# Rumble.net
KiCad netlist of a schematic drawn in Altium Designer
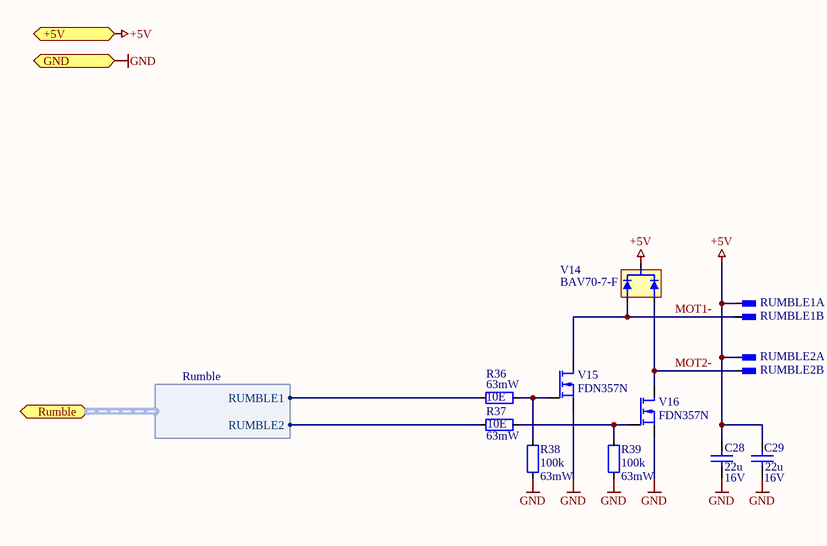
[diagram p0: Rumble.SchDoc]

(export (version "E")
  (design (tool "Eeschema 10.0.6"))
  (components
    (comp (ref "C28")
      (value "22u")
      (footprint "SMD_CAP_0805")
      (description "22µF ±10% 16V Ceramic Capacitor X5R 0805 (2012 Metric)")
      (fields (field (name "VALUE2") "16V") (field (name "Comment") "C_SMD_CER_22U_16V_10%_X5R_0805"))
      (libsource (lib "AM") (part "C_SMD_CER_22U_16V_10%_X5R_0805"))
    )
    (comp (ref "C29")
      (value "22u")
      (footprint "SMD_CAP_0805")
      (description "22µF ±10% 16V Ceramic Capacitor X5R 0805 (2012 Metric)")
      (fields (field (name "VALUE2") "16V") (field (name "Comment") "C_SMD_CER_22U_16V_10%_X5R_0805"))
      (libsource (lib "AM") (part "C_SMD_CER_22U_16V_10%_X5R_0805"))
    )
    (comp (ref "R36")
      (value "10E")
      (footprint "SMD_RES_0402")
      (description "10 Ohms ±0.5% 0.063W, 1/16W Chip Resistor 0402 (1005 Metric) Thin Film")
      (fields
        (field (name "VALUE2") "63mW")
        (field (name "Comment") "R_SMD_THINFILM_10E_0W063_0%5_50PPM_0402")
      )
      (libsource (lib "AM") (part "R_SMD_THINFILM_10E_0W063_0%5_50PPM_0402"))
    )
    (comp (ref "R37")
      (value "10E")
      (footprint "SMD_RES_0402")
      (description "10 Ohms ±0.5% 0.063W, 1/16W Chip Resistor 0402 (1005 Metric) Thin Film")
      (fields
        (field (name "VALUE2") "63mW")
        (field (name "Comment") "R_SMD_THINFILM_10E_0W063_0%5_50PPM_0402")
      )
      (libsource (lib "AM") (part "R_SMD_THINFILM_10E_0W063_0%5_50PPM_0402"))
    )
    (comp (ref "R38")
      (value "100k")
      (footprint "SMD_RES_0402")
      (description "100 kOhms ±1% 0.063W, 1/16W Chip Resistor 0402 (1005 Metric) Thin Film")
      (fields
        (field (name "VALUE2") "63mW")
        (field (name "Comment") "R_SMD_THINFILM_100K_0W063_1%_50PPM_0402")
      )
      (libsource (lib "AM") (part "R_SMD_THINFILM_100K_0W063_1%_50PPM_0402"))
    )
    (comp (ref "R39")
      (value "100k")
      (footprint "SMD_RES_0402")
      (description "100 kOhms ±1% 0.063W, 1/16W Chip Resistor 0402 (1005 Metric) Thin Film")
      (fields
        (field (name "VALUE2") "63mW")
        (field (name "Comment") "R_SMD_THINFILM_100K_0W063_1%_50PPM_0402")
      )
      (libsource (lib "AM") (part "R_SMD_THINFILM_100K_0W063_1%_50PPM_0402"))
    )
    (comp (ref "RUMBLE1")
      (value "X_CONNECTOR_P2.54_D0.9_1X2")
      (footprint "THT_CON_P2.54_D0.9_1X2")
      (description "Pitch 2.54, Diameter 0.9mm, 1 row, 2 columns")
      (libsource (lib "AM") (part "X_CONNECTOR_P2.54_D0.9_1X2"))
    )
    (comp (ref "RUMBLE2")
      (value "X_CONNECTOR_P2.54_D0.9_1X2")
      (footprint "THT_CON_P2.54_D0.9_1X2")
      (description "Pitch 2.54, Diameter 0.9mm, 1 row, 2 columns")
      (libsource (lib "AM") (part "X_CONNECTOR_P2.54_D0.9_1X2"))
    )
    (comp (ref "V14")
      (value "V_SMD_DIODE_ARRAY_75V_0A15_SOT23-3")
      (footprint "SMD_SOT_23_3")
      (fields (field (name "TYPE") "BAV70-7-F"))
      (libsource (lib "AM") (part "V_SMD_DIODE_ARRAY_75V_0A15_SOT23-3"))
    )
    (comp (ref "V15")
      (value "V_SMD_FET_NMOS_FDN357N_30V_1A9_4NC2_0W5_SOT-23-3")
      (footprint "SMD_SOT_23_3")
      (description "N-Channel Logic Level Enhancement Mode Field Effect Transistor")
      (fields (field (name "TYPE") "FDN357N"))
      (libsource (lib "AM") (part "V_SMD_FET_NMOS_FDN357N_30V_1A9_4NC2_0W5_SOT-23-3"))
    )
    (comp (ref "V16")
      (value "V_SMD_FET_NMOS_FDN357N_30V_1A9_4NC2_0W5_SOT-23-3")
      (footprint "SMD_SOT_23_3")
      (description "N-Channel Logic Level Enhancement Mode Field Effect Transistor")
      (fields (field (name "TYPE") "FDN357N"))
      (libsource (lib "AM") (part "V_SMD_FET_NMOS_FDN357N_30V_1A9_4NC2_0W5_SOT-23-3"))
    )
  )
  (nets
    (net (code "2") (name "+5V") (class "Default")
      (node (ref "C28") (pin "2") (pinfunction "2_2") (pintype "passive"))
      (node (ref "C29") (pin "2") (pinfunction "2_2") (pintype "passive"))
      (node (ref "RUMBLE1") (pin "1") (pinfunction "1_1") (pintype "passive"))
      (node (ref "RUMBLE2") (pin "1") (pinfunction "1_1") (pintype "passive"))
      (node (ref "V14") (pin "3") (pinfunction "Cathode_3") (pintype "passive"))
    )
    (net (code "3") (name "/MOT1-") (class "Default")
      (node (ref "RUMBLE1") (pin "2") (pinfunction "2_2") (pintype "passive"))
      (node (ref "V14") (pin "1") (pinfunction "Anode_1") (pintype "passive"))
      (node (ref "V15") (pin "3") (pinfunction "Drain_3") (pintype "passive"))
    )
    (net (code "4") (name "/MOT2-") (class "Default")
      (node (ref "RUMBLE2") (pin "2") (pinfunction "2_2") (pintype "passive"))
      (node (ref "V14") (pin "2") (pinfunction "Anode_2") (pintype "passive"))
      (node (ref "V16") (pin "3") (pinfunction "Drain_3") (pintype "passive"))
    )
    (net (code "5") (name "/RUMBLE1") (class "Default")
      (node (ref "R36") (pin "1") (pinfunction "1_1") (pintype "passive"))
    )
    (net (code "6") (name "/RUMBLE2") (class "Default")
      (node (ref "R37") (pin "1") (pinfunction "1_1") (pintype "passive"))
    )
    (net (code "8") (name "GND") (class "Default")
      (node (ref "C28") (pin "1") (pinfunction "1_1") (pintype "passive"))
      (node (ref "C29") (pin "1") (pinfunction "1_1") (pintype "passive"))
      (node (ref "R38") (pin "1") (pinfunction "1_1") (pintype "passive"))
      (node (ref "R39") (pin "1") (pinfunction "1_1") (pintype "passive"))
      (node (ref "V15") (pin "2") (pinfunction "Source_2") (pintype "passive"))
      (node (ref "V16") (pin "2") (pinfunction "Source_2") (pintype "passive"))
    )
    (net (code "9") (name "Net-(V15-Gate)") (class "Default")
      (node (ref "R36") (pin "2") (pinfunction "2_2") (pintype "passive"))
      (node (ref "R38") (pin "2") (pinfunction "2_2") (pintype "passive"))
      (node (ref "V15") (pin "1") (pinfunction "Gate_1") (pintype "passive"))
    )
    (net (code "10") (name "Net-(V16-Gate)") (class "Default")
      (node (ref "R37") (pin "2") (pinfunction "2_2") (pintype "passive"))
      (node (ref "R39") (pin "2") (pinfunction "2_2") (pintype "passive"))
      (node (ref "V16") (pin "1") (pinfunction "Gate_1") (pintype "passive"))
    )
  )
)
